# DIP_REFLOW.net
KiCad netlist of a schematic drawn in EAGLE
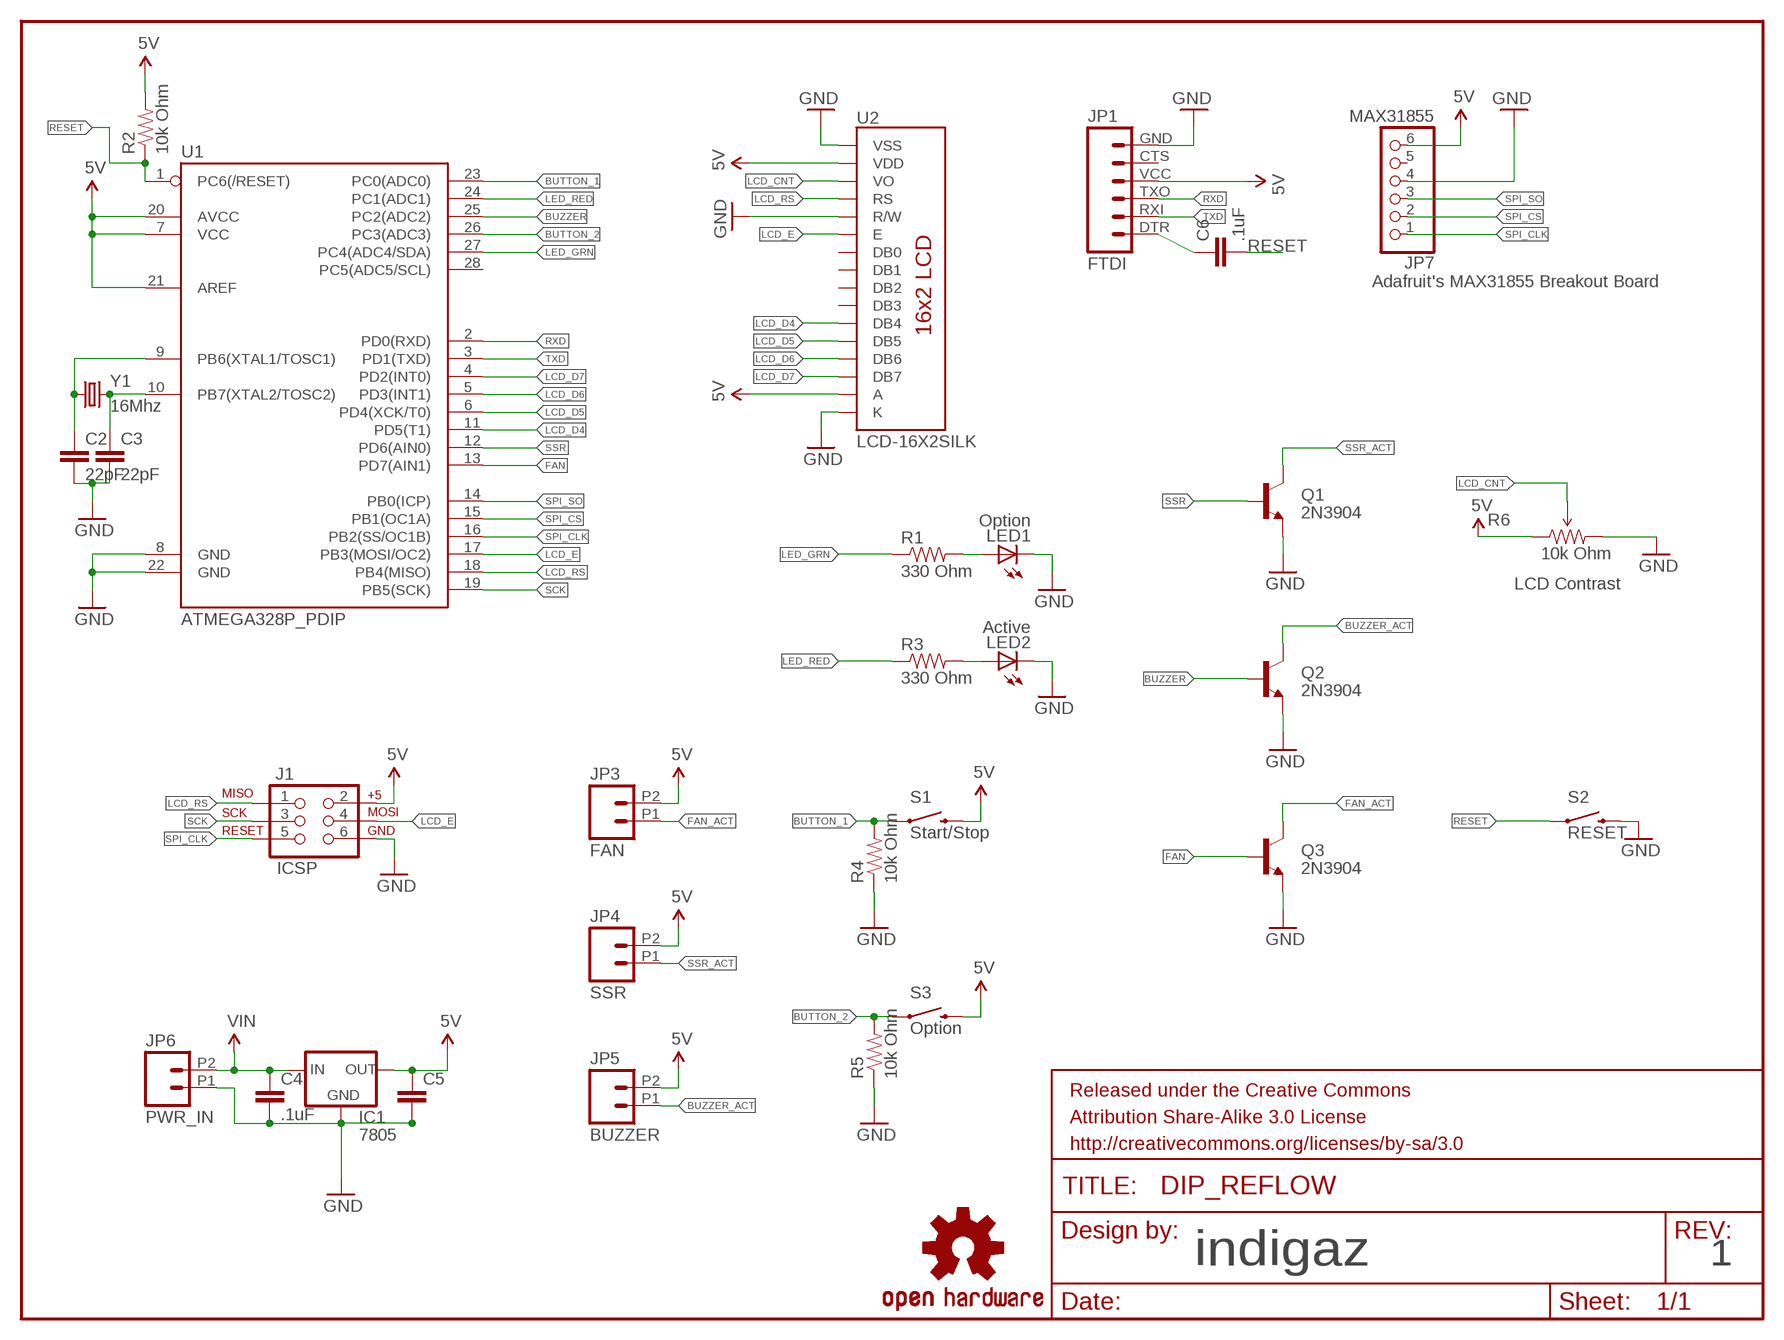
[diagram p0: schematic, sheet 1]

(export (version "E")
  (design (tool "Eeschema 10.0.6"))
  (components
    (comp (ref "C2")
      (value "22pF")
      (footprint "eagle-import:CAP-PTH-5MM")
      (libsource (lib "eagle-import") (part "CAPPTH1"))
    )
    (comp (ref "C3")
      (value "22pF")
      (footprint "eagle-import:CAP-PTH-5MM")
      (libsource (lib "eagle-import") (part "CAPPTH1"))
    )
    (comp (ref "C4")
      (value ".1uF")
      (footprint "eagle-import:CAP-PTH-5MM")
      (libsource (lib "eagle-import") (part "CAPPTH1"))
    )
    (comp (ref "C5")
      (value "CAPPTH1")
      (footprint "eagle-import:CAP-PTH-5MM")
      (libsource (lib "eagle-import") (part "CAPPTH1"))
    )
    (comp (ref "C6")
      (value ".1uF")
      (footprint "eagle-import:CAP-PTH-5MM")
      (libsource (lib "eagle-import") (part "CAPPTH1"))
    )
    (comp (ref "FRAME1")
      (value "FRAME-LETTER")
      (footprint "eagle-import:CREATIVE_COMMONS")
      (libsource (lib "eagle-import") (part "FRAME-LETTER"))
    )
    (comp (ref "IC1")
      (value "7805")
      (footprint "eagle-import:TO-220-ALT")
      (libsource (lib "eagle-import") (part "V_REG_78XX-TO-220"))
    )
    (comp (ref "J1")
      (value "ICSP")
      (footprint "eagle-import:2X3")
      (libsource (lib "eagle-import") (part "AVR_SPI_PRG_6PTH"))
    )
    (comp (ref "JP1")
      (value "FTDI")
      (footprint "eagle-import:FTDI_BASIC")
      (libsource (lib "eagle-import") (part "FTDI_BASICPTH"))
    )
    (comp (ref "JP3")
      (value "FAN")
      (footprint "eagle-import:1X02_2.54_SCREWTERM")
      (libsource (lib "eagle-import") (part "M022.54MM_SCREWTERM"))
    )
    (comp (ref "JP4")
      (value "SSR")
      (footprint "eagle-import:1X02_2.54_SCREWTERM")
      (libsource (lib "eagle-import") (part "M022.54MM_SCREWTERM"))
    )
    (comp (ref "JP5")
      (value "BUZZER")
      (footprint "eagle-import:1X02_2.54_SCREWTERM")
      (libsource (lib "eagle-import") (part "M022.54MM_SCREWTERM"))
    )
    (comp (ref "JP6")
      (value "PWR_IN")
      (footprint "eagle-import:1X02_2.54_SCREWTERM")
      (libsource (lib "eagle-import") (part "M022.54MM_SCREWTERM"))
    )
    (comp (ref "JP7")
      (value "MAX31855")
      (footprint "eagle-import:1X06")
      (libsource (lib "eagle-import") (part "PINHD-1X6"))
    )
    (comp (ref "LED1")
      (value "Option")
      (footprint "eagle-import:LED5MM")
      (libsource (lib "eagle-import") (part "LED5MM"))
    )
    (comp (ref "LED2")
      (value "Active")
      (footprint "eagle-import:LED5MM")
      (libsource (lib "eagle-import") (part "LED5MM"))
    )
    (comp (ref "LOGO1")
      (value "OSHW-LOGOL")
      (footprint "eagle-import:OSHW-LOGO-L")
      (libsource (lib "eagle-import") (part "OSHW-LOGOL"))
    )
    (comp (ref "Q1")
      (value "2N3904")
      (footprint "eagle-import:TO-92-AMMO")
      (libsource (lib "eagle-import") (part "TRANSISTOR_NPNTO-92-AMMO"))
    )
    (comp (ref "Q2")
      (value "2N3904")
      (footprint "eagle-import:TO-92-AMMO")
      (libsource (lib "eagle-import") (part "TRANSISTOR_NPNTO-92-AMMO"))
    )
    (comp (ref "Q3")
      (value "2N3904")
      (footprint "eagle-import:TO-92-AMMO")
      (libsource (lib "eagle-import") (part "TRANSISTOR_NPNTO-92-AMMO"))
    )
    (comp (ref "R1")
      (value "330 Ohm")
      (footprint "eagle-import:AXIAL-0.4")
      (libsource (lib "eagle-import") (part "RESISTORPTH-1/4W"))
    )
    (comp (ref "R2")
      (value "10k Ohm")
      (footprint "eagle-import:AXIAL-0.4")
      (libsource (lib "eagle-import") (part "RESISTORPTH-1/4W"))
    )
    (comp (ref "R3")
      (value "330 Ohm")
      (footprint "eagle-import:AXIAL-0.4")
      (libsource (lib "eagle-import") (part "RESISTORPTH-1/4W"))
    )
    (comp (ref "R4")
      (value "10k Ohm")
      (footprint "eagle-import:AXIAL-0.4")
      (libsource (lib "eagle-import") (part "RESISTORPTH-1/4W"))
    )
    (comp (ref "R5")
      (value "10k Ohm")
      (footprint "eagle-import:AXIAL-0.4")
      (libsource (lib "eagle-import") (part "RESISTORPTH-1/4W"))
    )
    (comp (ref "R6")
      (value "10k Ohm")
      (footprint "eagle-import:3386U")
      (libsource (lib "eagle-import") (part "TRIMPOT-PTH-KNOB"))
    )
    (comp (ref "S1")
      (value "Start/Stop")
      (footprint "eagle-import:TACTILE-PTH")
      (libsource (lib "eagle-import") (part "SWITCH-MOMENTARY-2PTH"))
    )
    (comp (ref "S2")
      (value "RESET")
      (footprint "eagle-import:TACTILE-PTH")
      (libsource (lib "eagle-import") (part "SWITCH-MOMENTARY-2PTH"))
    )
    (comp (ref "S3")
      (value "Option")
      (footprint "eagle-import:TACTILE-PTH")
      (libsource (lib "eagle-import") (part "SWITCH-MOMENTARY-2PTH"))
    )
    (comp (ref "U1")
      (value "ATMEGA328P_PDIP")
      (footprint "eagle-import:DIL28-3")
      (libsource (lib "eagle-import") (part "ATMEGA328P_PDIP"))
    )
    (comp (ref "U2")
      (value "LCD-16X2SILK")
      (footprint "eagle-import:LCD-16X2")
      (libsource (lib "eagle-import") (part "LCD-16X2SILK"))
    )
    (comp (ref "Y1")
      (value "16Mhz")
      (footprint "eagle-import:HC49US")
      (libsource (lib "eagle-import") (part "CRYSTALHC49US"))
    )
  )
  (nets
    (net (code "1") (name "5V") (class "Default")
      (node (ref "C5") (pin "1") (pinfunction "1_1") (pintype "passive"))
      (node (ref "IC1") (pin "OUT") (pinfunction "OUT_OUT") (pintype "output"))
      (node (ref "J1") (pin "2") (pinfunction "2_2") (pintype "passive"))
      (node (ref "JP1") (pin "VCC") (pinfunction "4_VCC") (pintype "passive"))
      (node (ref "JP3") (pin "P2") (pinfunction "2_P2") (pintype "passive"))
      (node (ref "JP4") (pin "P2") (pinfunction "2_P2") (pintype "passive"))
      (node (ref "JP5") (pin "P2") (pinfunction "2_P2") (pintype "passive"))
      (node (ref "JP7") (pin "6") (pinfunction "6_6") (pintype "passive"))
      (node (ref "R2") (pin "P$2") (pinfunction "2_P$2") (pintype "passive"))
      (node (ref "R6") (pin "1") (pinfunction "CCW_1") (pintype "passive"))
      (node (ref "S1") (pin "3") (pinfunction "2_3") (pintype "passive"))
      (node (ref "S3") (pin "3") (pinfunction "2_3") (pintype "passive"))
      (node (ref "U1") (pin "20") (pinfunction "AVCC_20") (pintype "bidirectional"))
      (node (ref "U1") (pin "21") (pinfunction "AREF_21") (pintype "bidirectional"))
      (node (ref "U1") (pin "7") (pinfunction "VCC_7") (pintype "bidirectional"))
      (node (ref "U2") (pin "15") (pinfunction "A_15") (pintype "power_in"))
      (node (ref "U2") (pin "2") (pinfunction "VDD_2") (pintype "power_in"))
    )
    (net (code "2") (name "BUTTON_1") (class "Default")
      (node (ref "R4") (pin "P$2") (pinfunction "2_P$2") (pintype "passive"))
      (node (ref "S1") (pin "1") (pinfunction "1_1") (pintype "passive"))
      (node (ref "U1") (pin "23") (pinfunction "PC0(ADC0)_23") (pintype "bidirectional"))
    )
    (net (code "3") (name "BUTTON_2") (class "Default")
      (node (ref "R5") (pin "P$2") (pinfunction "2_P$2") (pintype "passive"))
      (node (ref "S3") (pin "1") (pinfunction "1_1") (pintype "passive"))
      (node (ref "U1") (pin "26") (pinfunction "PC3(ADC3)_26") (pintype "bidirectional"))
    )
    (net (code "4") (name "BUZZER") (class "Default")
      (node (ref "Q2") (pin "2") (pinfunction "B_2") (pintype "passive"))
      (node (ref "U1") (pin "25") (pinfunction "PC2(ADC2)_25") (pintype "bidirectional"))
    )
    (net (code "5") (name "BUZZER_ACT") (class "Default")
      (node (ref "JP5") (pin "P1") (pinfunction "1_P1") (pintype "passive"))
      (node (ref "Q2") (pin "3") (pinfunction "C_3") (pintype "passive"))
    )
    (net (code "6") (name "FAN") (class "Default")
      (node (ref "Q3") (pin "2") (pinfunction "B_2") (pintype "passive"))
      (node (ref "U1") (pin "13") (pinfunction "PD7(AIN1)_13") (pintype "bidirectional"))
    )
    (net (code "7") (name "FAN_ACT") (class "Default")
      (node (ref "JP3") (pin "P1") (pinfunction "1_P1") (pintype "passive"))
      (node (ref "Q3") (pin "3") (pinfunction "C_3") (pintype "passive"))
    )
    (net (code "8") (name "GND") (class "Default")
      (node (ref "C2") (pin "2") (pinfunction "2_2") (pintype "passive"))
      (node (ref "C3") (pin "2") (pinfunction "2_2") (pintype "passive"))
      (node (ref "C4") (pin "2") (pinfunction "2_2") (pintype "passive"))
      (node (ref "C5") (pin "2") (pinfunction "2_2") (pintype "passive"))
      (node (ref "IC1") (pin "GND") (pinfunction "GND_GND") (pintype "input"))
      (node (ref "J1") (pin "6") (pinfunction "6_6") (pintype "passive"))
      (node (ref "JP1") (pin "GND") (pinfunction "6_GND") (pintype "passive"))
      (node (ref "JP6") (pin "P1") (pinfunction "1_P1") (pintype "passive"))
      (node (ref "JP7") (pin "4") (pinfunction "4_4") (pintype "passive"))
      (node (ref "LED1") (pin "K") (pinfunction "C_K") (pintype "passive"))
      (node (ref "LED2") (pin "K") (pinfunction "C_K") (pintype "passive"))
      (node (ref "Q1") (pin "1") (pinfunction "E_1") (pintype "passive"))
      (node (ref "Q2") (pin "1") (pinfunction "E_1") (pintype "passive"))
      (node (ref "Q3") (pin "1") (pinfunction "E_1") (pintype "passive"))
      (node (ref "R4") (pin "P$1") (pinfunction "1_P$1") (pintype "passive"))
      (node (ref "R5") (pin "P$1") (pinfunction "1_P$1") (pintype "passive"))
      (node (ref "R6") (pin "3") (pinfunction "CW_3") (pintype "passive"))
      (node (ref "S2") (pin "3") (pinfunction "2_3") (pintype "passive"))
      (node (ref "U1") (pin "22") (pinfunction "GND_22") (pintype "bidirectional"))
      (node (ref "U1") (pin "8") (pinfunction "GND_8") (pintype "bidirectional"))
      (node (ref "U2") (pin "1") (pinfunction "VSS_1") (pintype "power_in"))
      (node (ref "U2") (pin "16") (pinfunction "K_16") (pintype "power_in"))
      (node (ref "U2") (pin "5") (pinfunction "R/W_5") (pintype "input"))
    )
    (net (code "9") (name "LCD_CNT") (class "Default")
      (node (ref "R6") (pin "2") (pinfunction "WIPER_2") (pintype "passive"))
      (node (ref "U2") (pin "3") (pinfunction "VO_3") (pintype "bidirectional"))
    )
    (net (code "10") (name "LCD_D4") (class "Default")
      (node (ref "U1") (pin "11") (pinfunction "PD5(T1)_11") (pintype "bidirectional"))
      (node (ref "U2") (pin "11") (pinfunction "DB4_11") (pintype "bidirectional"))
    )
    (net (code "11") (name "LCD_D5") (class "Default")
      (node (ref "U1") (pin "6") (pinfunction "PD4(XCK/T0)_6") (pintype "bidirectional"))
      (node (ref "U2") (pin "12") (pinfunction "DB5_12") (pintype "bidirectional"))
    )
    (net (code "12") (name "LCD_D6") (class "Default")
      (node (ref "U1") (pin "5") (pinfunction "PD3(INT1)_5") (pintype "bidirectional"))
      (node (ref "U2") (pin "13") (pinfunction "DB6_13") (pintype "bidirectional"))
    )
    (net (code "13") (name "LCD_D7") (class "Default")
      (node (ref "U1") (pin "4") (pinfunction "PD2(INT0)_4") (pintype "bidirectional"))
      (node (ref "U2") (pin "14") (pinfunction "DB7_14") (pintype "bidirectional"))
    )
    (net (code "14") (name "LCD_E") (class "Default")
      (node (ref "J1") (pin "4") (pinfunction "4_4") (pintype "passive"))
      (node (ref "U1") (pin "17") (pinfunction "PB3(MOSI/OC2)_17") (pintype "bidirectional"))
      (node (ref "U2") (pin "6") (pinfunction "E_6") (pintype "input"))
    )
    (net (code "15") (name "LCD_RS") (class "Default")
      (node (ref "J1") (pin "1") (pinfunction "1_1") (pintype "passive"))
      (node (ref "U1") (pin "18") (pinfunction "PB4(MISO)_18") (pintype "bidirectional"))
      (node (ref "U2") (pin "4") (pinfunction "RS_4") (pintype "input"))
    )
    (net (code "16") (name "LED_GRN") (class "Default")
      (node (ref "R1") (pin "P$1") (pinfunction "1_P$1") (pintype "passive"))
      (node (ref "U1") (pin "27") (pinfunction "PC4(ADC4/SDA)_27") (pintype "bidirectional"))
    )
    (net (code "17") (name "LED_RED") (class "Default")
      (node (ref "R3") (pin "P$1") (pinfunction "1_P$1") (pintype "passive"))
      (node (ref "U1") (pin "24") (pinfunction "PC1(ADC1)_24") (pintype "bidirectional"))
    )
    (net (code "18") (name "Net-(JP1-1)") (class "Default")
      (node (ref "C6") (pin "1") (pinfunction "1_1") (pintype "passive"))
      (node (ref "JP1") (pin "DTR") (pinfunction "1_DTR") (pintype "passive"))
    )
    (net (code "19") (name "Net-(R1-2)") (class "Default")
      (node (ref "LED1") (pin "A") (pinfunction "A_A") (pintype "passive"))
      (node (ref "R1") (pin "P$2") (pinfunction "2_P$2") (pintype "passive"))
    )
    (net (code "20") (name "Net-(R3-2)") (class "Default")
      (node (ref "LED2") (pin "A") (pinfunction "A_A") (pintype "passive"))
      (node (ref "R3") (pin "P$2") (pinfunction "2_P$2") (pintype "passive"))
    )
    (net (code "21") (name "Net-(U1-PB6(XTAL1{slash}TOSC1))") (class "Default")
      (node (ref "C2") (pin "1") (pinfunction "1_1") (pintype "passive"))
      (node (ref "U1") (pin "9") (pinfunction "PB6(XTAL1/TOSC1)_9") (pintype "bidirectional"))
      (node (ref "Y1") (pin "1") (pinfunction "1_1") (pintype "passive"))
    )
    (net (code "22") (name "Net-(U1-PB7(XTAL2{slash}TOSC2))") (class "Default")
      (node (ref "C3") (pin "1") (pinfunction "1_1") (pintype "passive"))
      (node (ref "U1") (pin "10") (pinfunction "PB7(XTAL2/TOSC2)_10") (pintype "bidirectional"))
      (node (ref "Y1") (pin "2") (pinfunction "2_2") (pintype "passive"))
    )
    (net (code "23") (name "RESET") (class "Default")
      (node (ref "C6") (pin "2") (pinfunction "2_2") (pintype "passive"))
      (node (ref "R2") (pin "P$1") (pinfunction "1_P$1") (pintype "passive"))
      (node (ref "S2") (pin "1") (pinfunction "1_1") (pintype "passive"))
      (node (ref "U1") (pin "1") (pinfunction "PC6(/RESET)_1") (pintype "bidirectional"))
    )
    (net (code "24") (name "RXD") (class "Default")
      (node (ref "JP1") (pin "TXO") (pinfunction "3_TXO") (pintype "passive"))
      (node (ref "U1") (pin "2") (pinfunction "PD0(RXD)_2") (pintype "bidirectional"))
    )
    (net (code "25") (name "SCK") (class "Default")
      (node (ref "J1") (pin "3") (pinfunction "3_3") (pintype "passive"))
      (node (ref "U1") (pin "19") (pinfunction "PB5(SCK)_19") (pintype "bidirectional"))
    )
    (net (code "26") (name "SPI_CLK") (class "Default")
      (node (ref "J1") (pin "5") (pinfunction "5_5") (pintype "passive"))
      (node (ref "JP7") (pin "1") (pinfunction "1_1") (pintype "passive"))
      (node (ref "U1") (pin "16") (pinfunction "PB2(SS/OC1B)_16") (pintype "bidirectional"))
    )
    (net (code "27") (name "SPI_CS") (class "Default")
      (node (ref "JP7") (pin "2") (pinfunction "2_2") (pintype "passive"))
      (node (ref "U1") (pin "15") (pinfunction "PB1(OC1A)_15") (pintype "bidirectional"))
    )
    (net (code "28") (name "SPI_SO") (class "Default")
      (node (ref "JP7") (pin "3") (pinfunction "3_3") (pintype "passive"))
      (node (ref "U1") (pin "14") (pinfunction "PB0(ICP)_14") (pintype "bidirectional"))
    )
    (net (code "29") (name "SSR") (class "Default")
      (node (ref "Q1") (pin "2") (pinfunction "B_2") (pintype "passive"))
      (node (ref "U1") (pin "12") (pinfunction "PD6(AIN0)_12") (pintype "bidirectional"))
    )
    (net (code "30") (name "SSR_ACT") (class "Default")
      (node (ref "JP4") (pin "P1") (pinfunction "1_P1") (pintype "passive"))
      (node (ref "Q1") (pin "3") (pinfunction "C_3") (pintype "passive"))
    )
    (net (code "31") (name "TXD") (class "Default")
      (node (ref "JP1") (pin "RXI") (pinfunction "2_RXI") (pintype "passive"))
      (node (ref "U1") (pin "3") (pinfunction "PD1(TXD)_3") (pintype "bidirectional"))
    )
    (net (code "32") (name "VIN") (class "Default")
      (node (ref "C4") (pin "1") (pinfunction "1_1") (pintype "passive"))
      (node (ref "IC1") (pin "IN") (pinfunction "IN_IN") (pintype "input"))
      (node (ref "JP6") (pin "P2") (pinfunction "2_P2") (pintype "passive"))
    )
    (net (code "33") (name "unconnected-(JP1-5-PadCTS)") (class "Default")
      (node (ref "JP1") (pin "CTS") (pinfunction "5_CTS") (pintype "passive"))
    )
    (net (code "34") (name "unconnected-(JP7-Pad5)") (class "Default")
      (node (ref "JP7") (pin "5") (pinfunction "5_5") (pintype "passive"))
    )
    (net (code "35") (name "unconnected-(U1-PC5(ADC5{slash}SCL)-Pad28)") (class "Default")
      (node (ref "U1") (pin "28") (pinfunction "PC5(ADC5/SCL)_28") (pintype "bidirectional"))
    )
    (net (code "36") (name "unconnected-(U2-DB0-Pad7)") (class "Default")
      (node (ref "U2") (pin "7") (pinfunction "DB0_7") (pintype "bidirectional"))
    )
    (net (code "37") (name "unconnected-(U2-DB1-Pad8)") (class "Default")
      (node (ref "U2") (pin "8") (pinfunction "DB1_8") (pintype "bidirectional"))
    )
    (net (code "38") (name "unconnected-(U2-DB2-Pad9)") (class "Default")
      (node (ref "U2") (pin "9") (pinfunction "DB2_9") (pintype "bidirectional"))
    )
    (net (code "39") (name "unconnected-(U2-DB3-Pad10)") (class "Default")
      (node (ref "U2") (pin "10") (pinfunction "DB3_10") (pintype "bidirectional"))
    )
  )
)
